# airball_sensor_board_v4.net
KiCad netlist of a schematic drawn in EAGLE
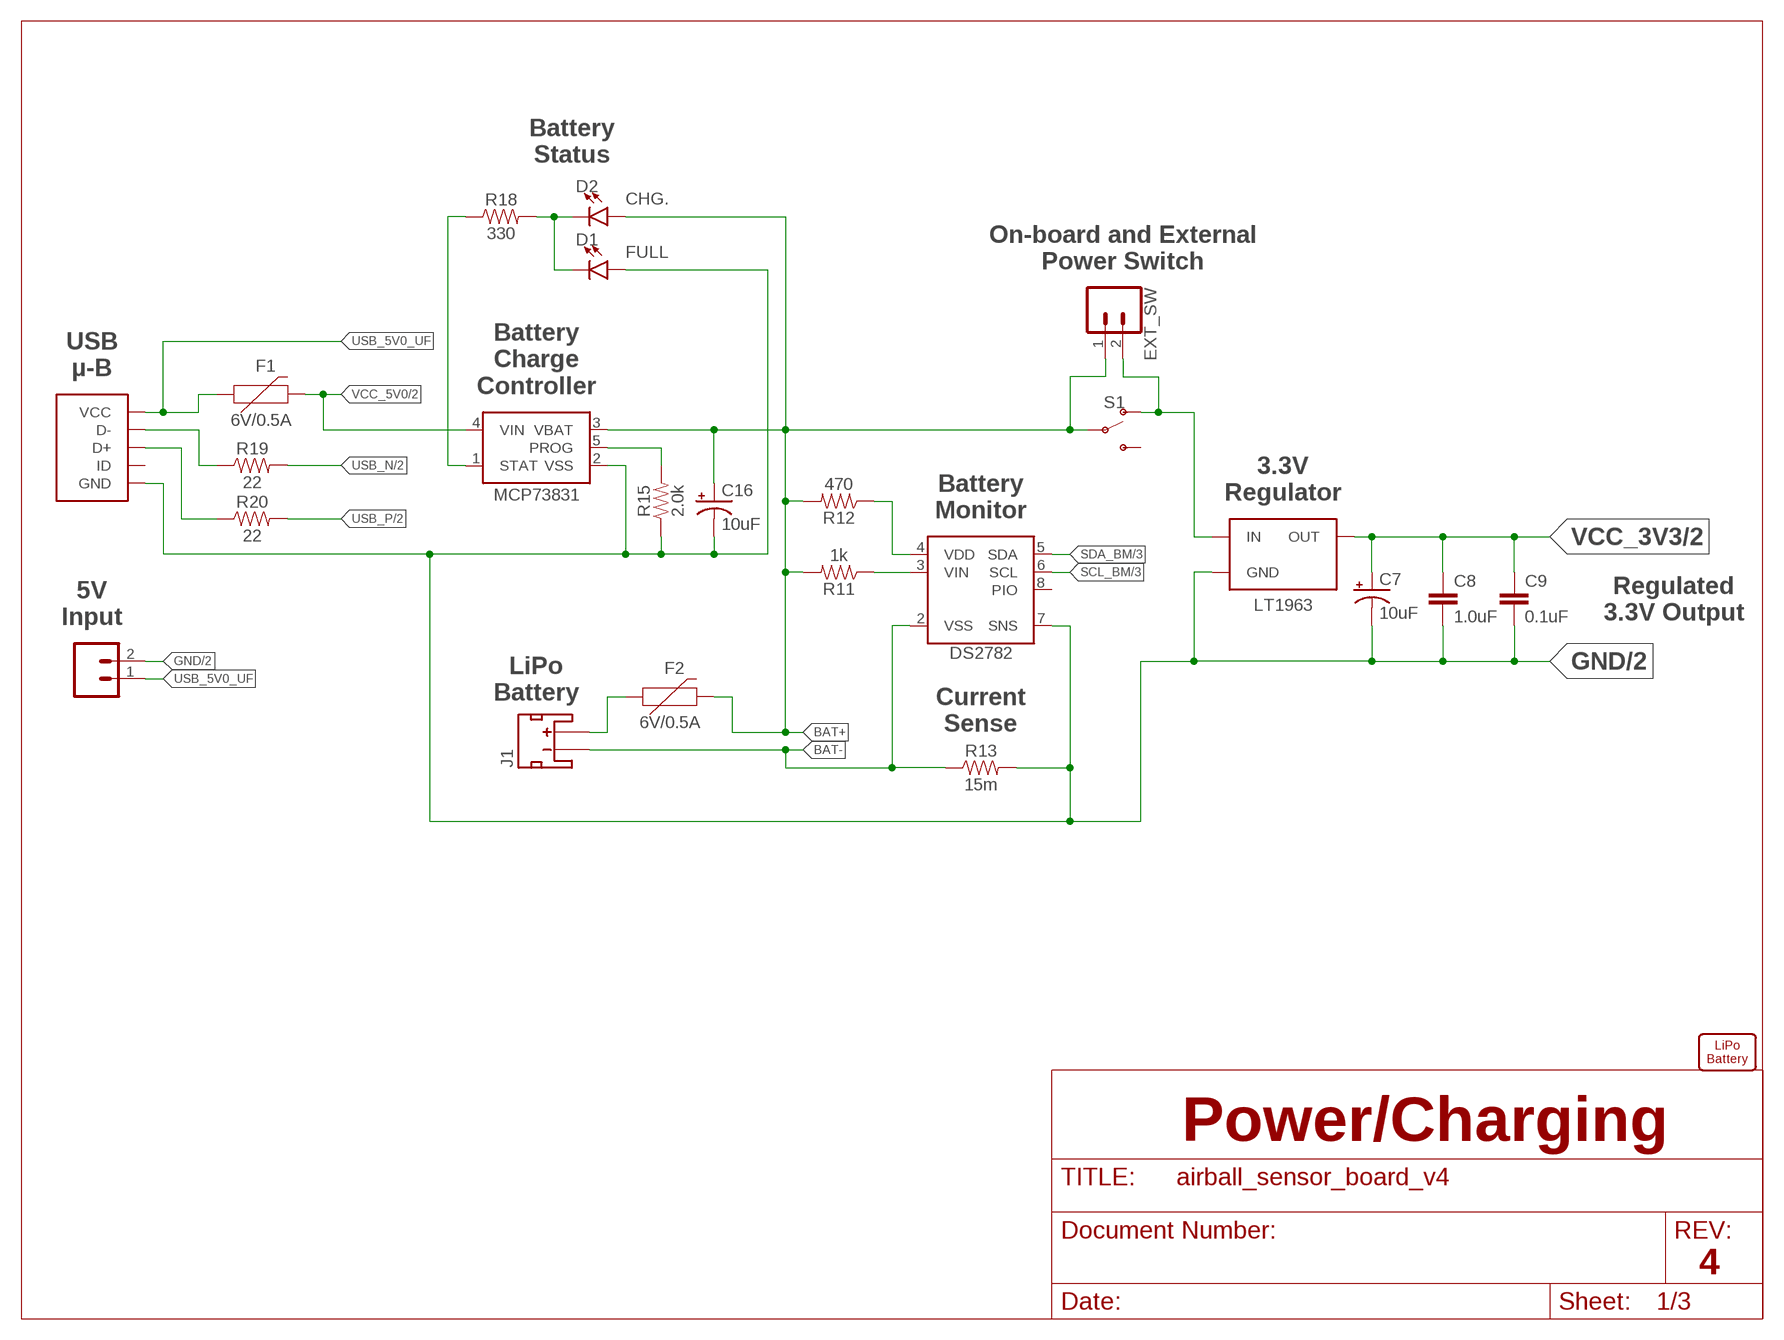
[diagram p0: schematic, sheet 1]
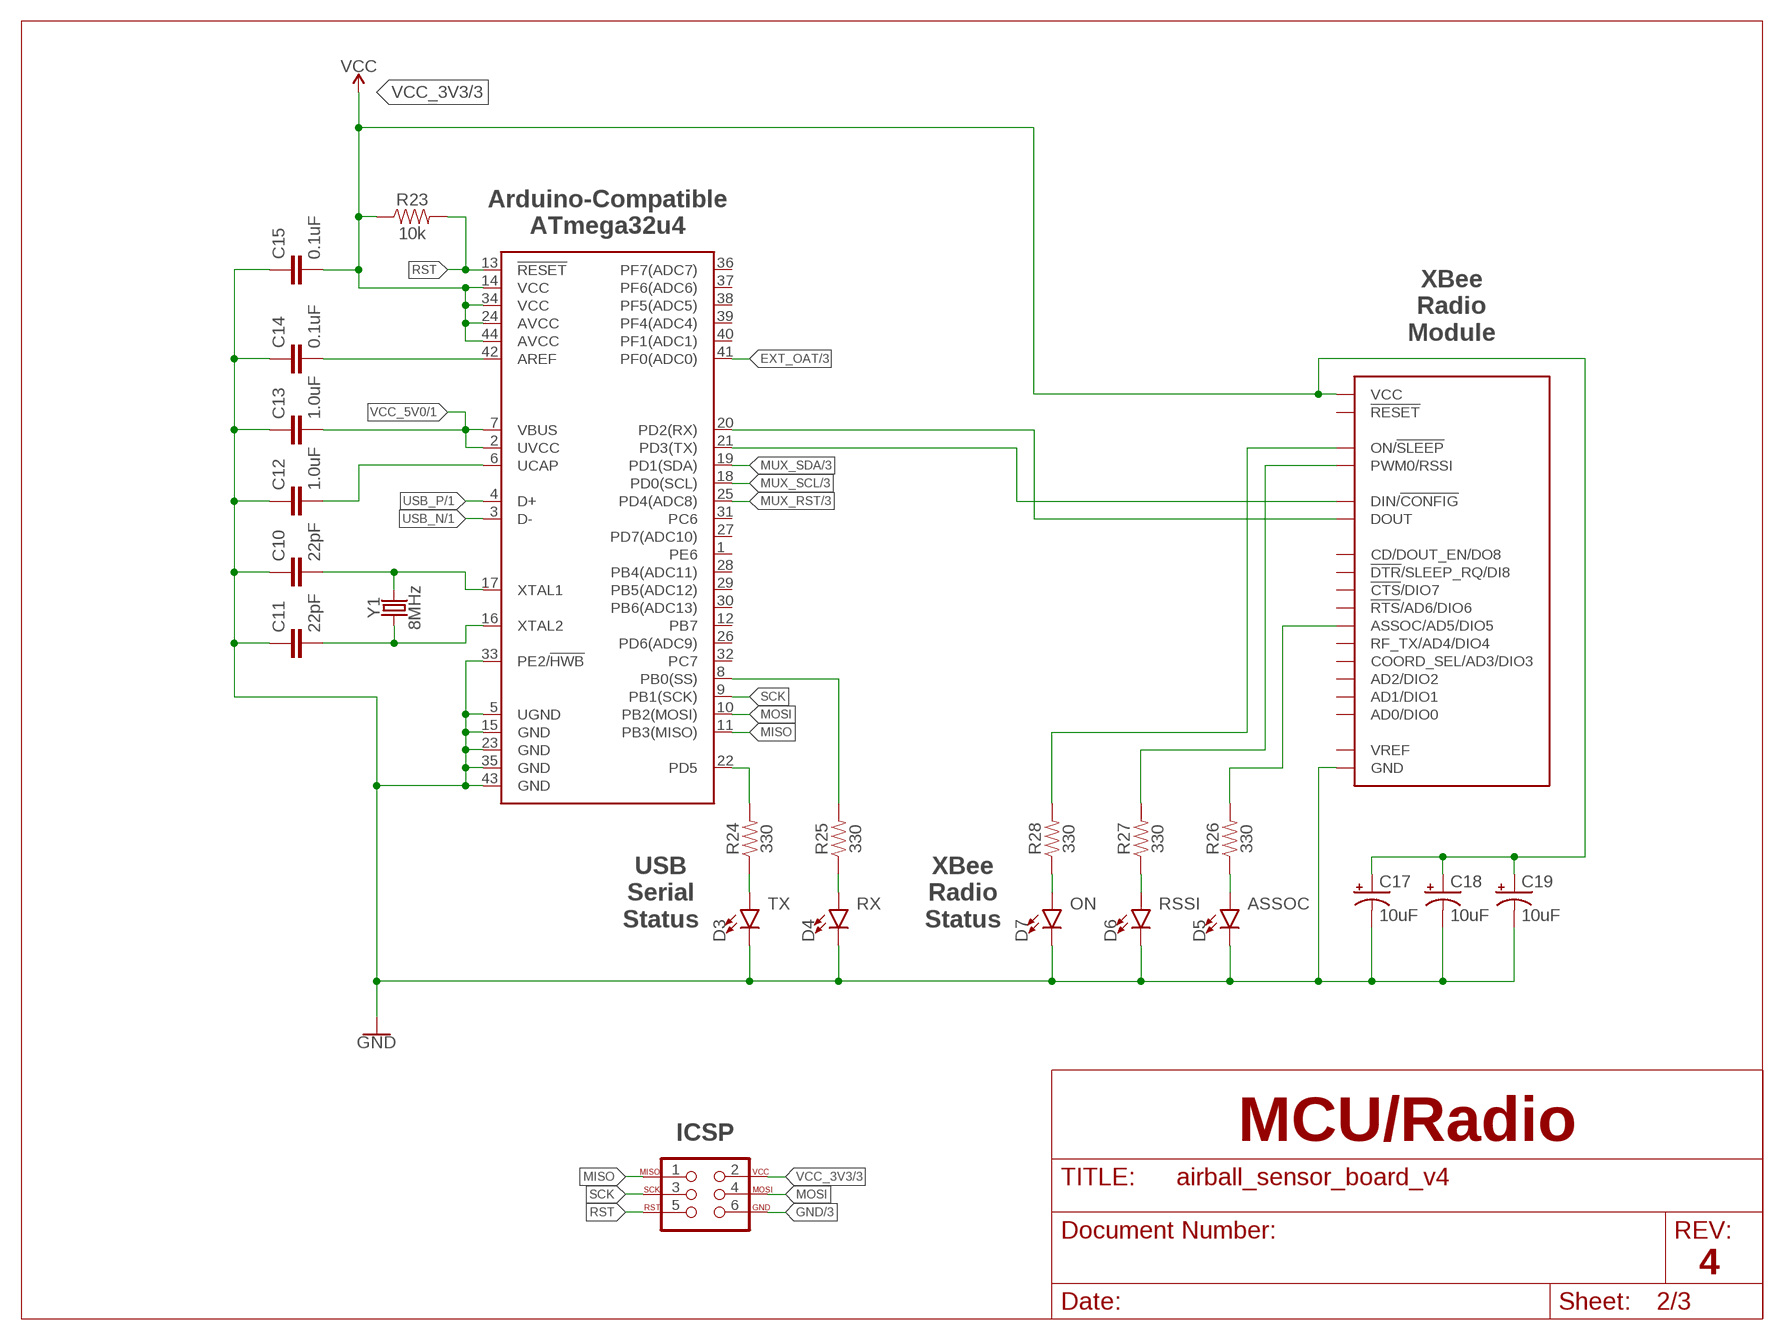
[diagram p1: schematic, sheet 2]
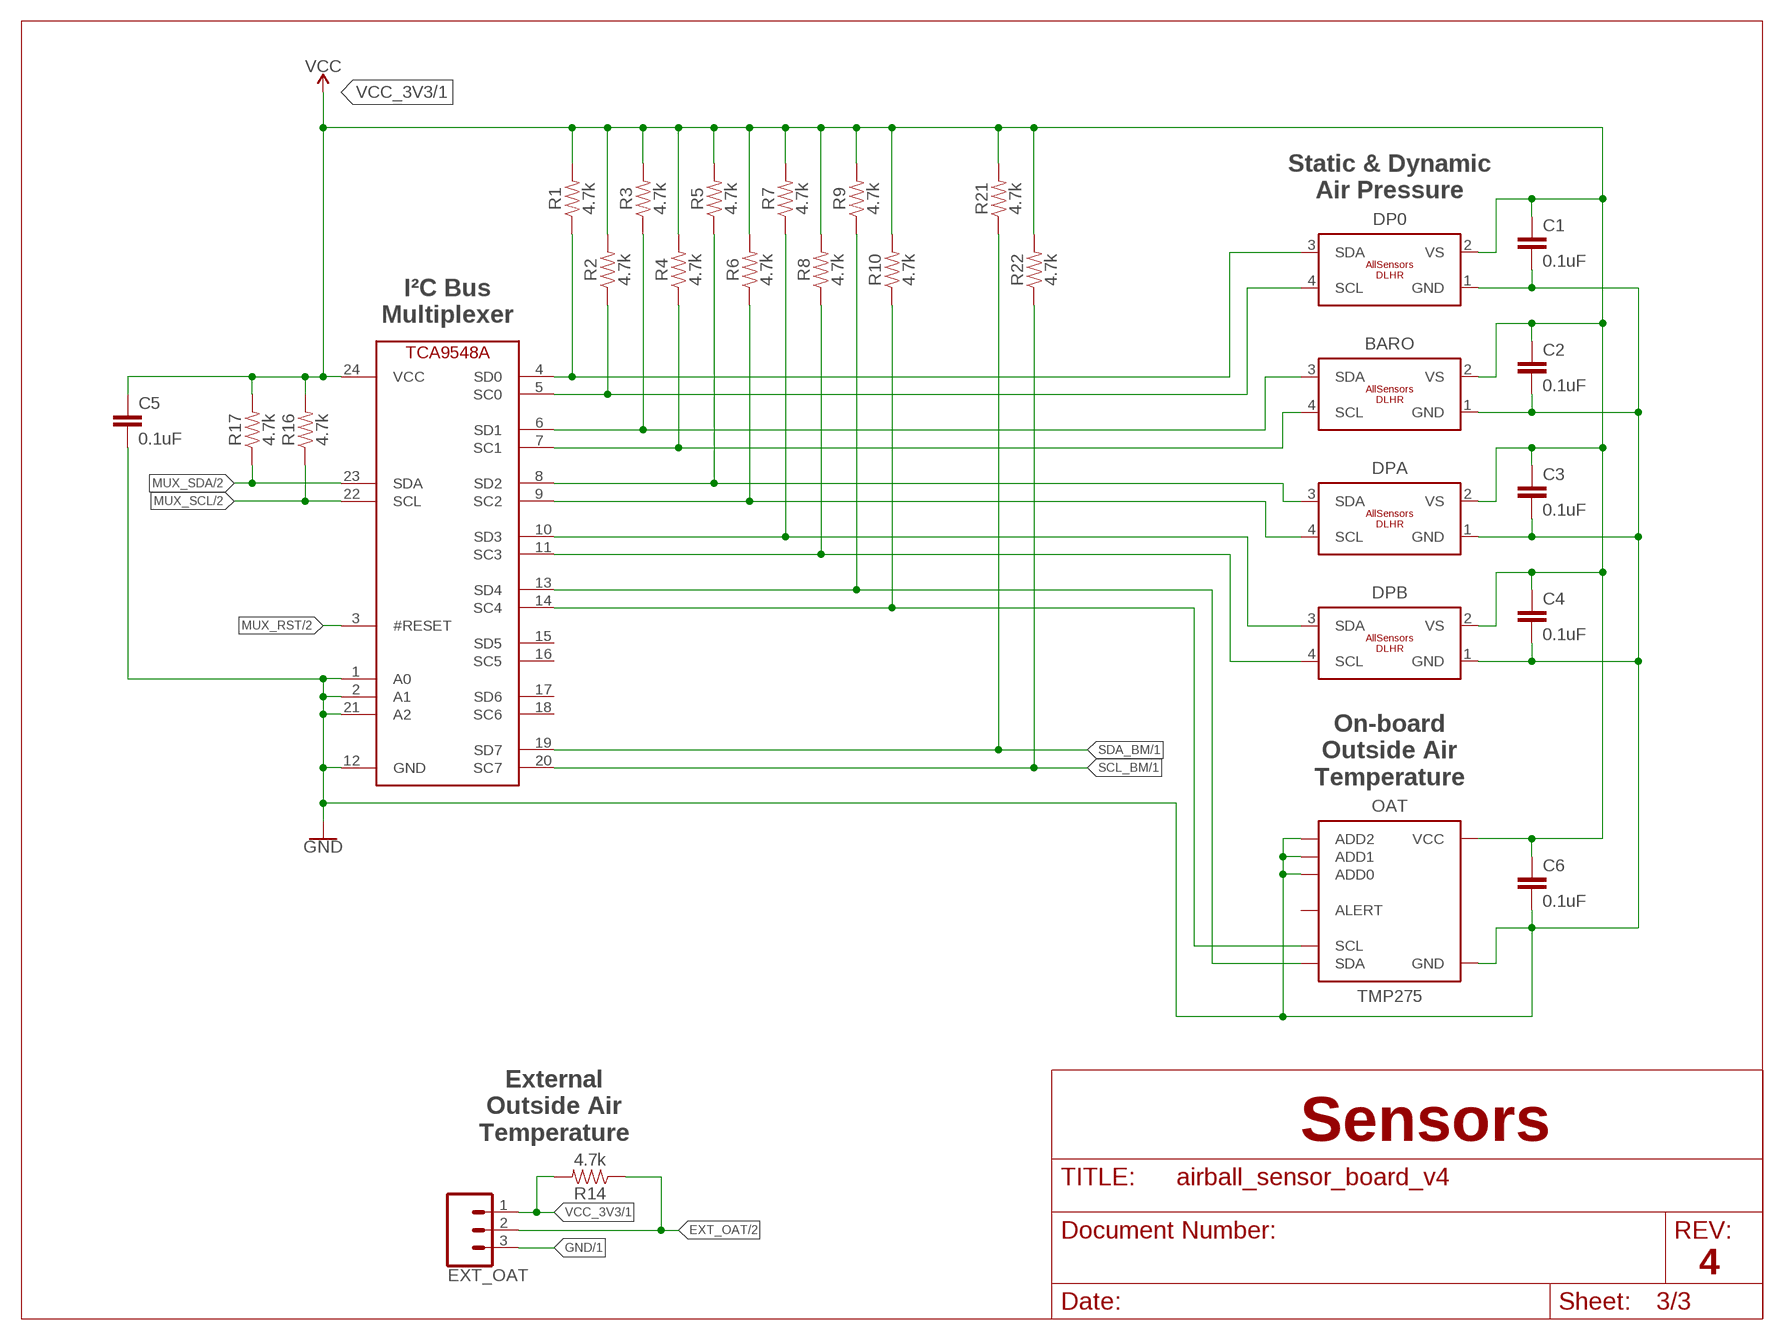
[diagram p2: schematic, sheet 3]

(export (version "E")
  (design (tool "Eeschema 10.0.6"))
  (components
    (comp (ref "BM")
      (value "DS2782")
      (footprint "eagle-import:TSSOP8")
      (libsource (lib "eagle-import") (part "DS2782"))
    )
    (comp (ref "C7")
      (value "10uF")
      (footprint "eagle-import:EIA3216")
      (libsource (lib "eagle-import") (part "10UF-POLAR-EIA3216-16V-10%(TANT)"))
    )
    (comp (ref "C8")
      (value "1.0uF")
      (footprint "eagle-import:0603")
      (libsource (lib "eagle-import") (part "1.0UF-0603-16V-10%"))
    )
    (comp (ref "C9")
      (value "0.1uF")
      (footprint "eagle-import:0603")
      (libsource (lib "eagle-import") (part "0.1UF-0603-25V-5%"))
    )
    (comp (ref "C16")
      (value "10uF")
      (footprint "eagle-import:EIA3216")
      (libsource (lib "eagle-import") (part "10UF-POLAR-EIA3216-16V-10%(TANT)"))
    )
    (comp (ref "CC")
      (value "MCP73831")
      (footprint "eagle-import:SOT23-5")
      (libsource (lib "eagle-import") (part "MCP73831"))
    )
    (comp (ref "D1")
      (value "LED0603")
      (footprint "eagle-import:LED-0603")
      (libsource (lib "eagle-import") (part "LED0603"))
    )
    (comp (ref "D2")
      (value "LED0603")
      (footprint "eagle-import:LED-0603")
      (libsource (lib "eagle-import") (part "LED0603"))
    )
    (comp (ref "EXT_POWER")
      (value "CONN_02")
      (footprint "eagle-import:1X02")
      (libsource (lib "eagle-import") (part "CONN_02"))
    )
    (comp (ref "EXT_SW")
      (value "CONN_02")
      (footprint "eagle-import:1X02")
      (libsource (lib "eagle-import") (part "CONN_02"))
    )
    (comp (ref "F1")
      (value "6V/0.5A")
      (footprint "eagle-import:1206")
      (libsource (lib "eagle-import") (part "PPTC_HALF-AMP"))
    )
    (comp (ref "F2")
      (value "6V/0.5A")
      (footprint "eagle-import:1206")
      (libsource (lib "eagle-import") (part "PPTC_HALF-AMP"))
    )
    (comp (ref "J1")
      (value "JST_2MM_MALE")
      (footprint "eagle-import:JST-2-SMD")
      (libsource (lib "eagle-import") (part "JST_2MM_MALE"))
    )
    (comp (ref "JP1")
      (value "USB_MICROB_PLUG")
      (footprint "eagle-import:USB_MICRO_B_TYCO")
      (libsource (lib "eagle-import") (part "USB_MICROB_PLUG"))
    )
    (comp (ref "R11")
      (value "1k")
      (footprint "eagle-import:0603")
      (libsource (lib "eagle-import") (part "1KOHM-0603-1/10W-1%"))
    )
    (comp (ref "R12")
      (value "470")
      (footprint "eagle-import:0603")
      (libsource (lib "eagle-import") (part "470OHM-0603-1/10W-1%"))
    )
    (comp (ref "R13")
      (value "15m")
      (footprint "eagle-import:1206")
      (libsource (lib "eagle-import") (part "RESISTOR1206"))
    )
    (comp (ref "R15")
      (value "2.0k")
      (footprint "eagle-import:0603")
      (libsource (lib "eagle-import") (part "2.0KOHM-0603-1/10W-5%"))
    )
    (comp (ref "R18")
      (value "330")
      (footprint "eagle-import:0603")
      (libsource (lib "eagle-import") (part "330OHM-0603-1/10W-1%"))
    )
    (comp (ref "R19")
      (value "22")
      (footprint "eagle-import:0603")
      (libsource (lib "eagle-import") (part "22OHM-0603-1/10W-1%"))
    )
    (comp (ref "R20")
      (value "22")
      (footprint "eagle-import:0603")
      (libsource (lib "eagle-import") (part "22OHM-0603-1/10W-1%"))
    )
    (comp (ref "S1")
      (value "SWITCH-SPDT-SMD-RIGHT-ANGLE")
      (footprint "eagle-import:SWITCH_SPST_SMD_A")
      (libsource (lib "eagle-import") (part "SWITCH-SPDT-SMD-RIGHT-ANGLE"))
    )
    (comp (ref "U$3")
      (value "LIPO_BATTERY_OUTLINE-1000MAH")
      (footprint "eagle-import:SPARKFUN_LIPO_1000MAH")
      (libsource (lib "eagle-import") (part "LIPO_BATTERY_OUTLINE-1000MAH"))
    )
    (comp (ref "VREG")
      (value "LT1963")
      (footprint "eagle-import:SOT223-3")
      (libsource (lib "eagle-import") (part "LT1963"))
    )
    (comp (ref "BARO")
      (value "ALLSENSORS_DLHR_I2C-E1BD")
      (footprint "eagle-import:ALLSENSORS_E1BD")
      (libsource (lib "eagle-import") (part "ALLSENSORS_DLHR_I2C-E1BD"))
    )
    (comp (ref "C1")
      (value "0.1uF")
      (footprint "eagle-import:0603")
      (libsource (lib "eagle-import") (part "0.1UF-0603-25V-5%"))
    )
    (comp (ref "C2")
      (value "0.1uF")
      (footprint "eagle-import:0603")
      (libsource (lib "eagle-import") (part "0.1UF-0603-25V-5%"))
    )
    (comp (ref "C3")
      (value "0.1uF")
      (footprint "eagle-import:0603")
      (libsource (lib "eagle-import") (part "0.1UF-0603-25V-5%"))
    )
    (comp (ref "C4")
      (value "0.1uF")
      (footprint "eagle-import:0603")
      (libsource (lib "eagle-import") (part "0.1UF-0603-25V-5%"))
    )
    (comp (ref "C5")
      (value "0.1uF")
      (footprint "eagle-import:0603")
      (libsource (lib "eagle-import") (part "0.1UF-0603-25V-5%"))
    )
    (comp (ref "C6")
      (value "0.1uF")
      (footprint "eagle-import:0603")
      (libsource (lib "eagle-import") (part "0.1UF-0603-25V-5%"))
    )
    (comp (ref "DP0")
      (value "ALLSENSORS_DLHR_I2C-E1BD")
      (footprint "eagle-import:ALLSENSORS_E1BD")
      (libsource (lib "eagle-import") (part "ALLSENSORS_DLHR_I2C-E1BD"))
    )
    (comp (ref "DPA")
      (value "ALLSENSORS_DLHR_I2C-E1BD")
      (footprint "eagle-import:ALLSENSORS_E1BD")
      (libsource (lib "eagle-import") (part "ALLSENSORS_DLHR_I2C-E1BD"))
    )
    (comp (ref "DPB")
      (value "ALLSENSORS_DLHR_I2C-E1BD")
      (footprint "eagle-import:ALLSENSORS_E1BD")
      (libsource (lib "eagle-import") (part "ALLSENSORS_DLHR_I2C-E1BD"))
    )
    (comp (ref "EXT_OAT")
      (value "CONN_03")
      (footprint "eagle-import:1X03")
      (libsource (lib "eagle-import") (part "CONN_03"))
    )
    (comp (ref "MUX")
      (value "TCA9548ATSSOP24")
      (footprint "eagle-import:TSSOP24")
      (libsource (lib "eagle-import") (part "TCA9548ATSSOP24"))
    )
    (comp (ref "OAT")
      (value "TMP275")
      (footprint "eagle-import:SOIC8")
      (libsource (lib "eagle-import") (part "LM75-8PIN"))
    )
    (comp (ref "R1")
      (value "4.7k")
      (footprint "eagle-import:0603")
      (libsource (lib "eagle-import") (part "4.7KOHM-0603-1/10W-1%"))
    )
    (comp (ref "R2")
      (value "4.7k")
      (footprint "eagle-import:0603")
      (libsource (lib "eagle-import") (part "4.7KOHM-0603-1/10W-1%"))
    )
    (comp (ref "R3")
      (value "4.7k")
      (footprint "eagle-import:0603")
      (libsource (lib "eagle-import") (part "4.7KOHM-0603-1/10W-1%"))
    )
    (comp (ref "R4")
      (value "4.7k")
      (footprint "eagle-import:0603")
      (libsource (lib "eagle-import") (part "4.7KOHM-0603-1/10W-1%"))
    )
    (comp (ref "R5")
      (value "4.7k")
      (footprint "eagle-import:0603")
      (libsource (lib "eagle-import") (part "4.7KOHM-0603-1/10W-1%"))
    )
    (comp (ref "R6")
      (value "4.7k")
      (footprint "eagle-import:0603")
      (libsource (lib "eagle-import") (part "4.7KOHM-0603-1/10W-1%"))
    )
    (comp (ref "R7")
      (value "4.7k")
      (footprint "eagle-import:0603")
      (libsource (lib "eagle-import") (part "4.7KOHM-0603-1/10W-1%"))
    )
    (comp (ref "R8")
      (value "4.7k")
      (footprint "eagle-import:0603")
      (libsource (lib "eagle-import") (part "4.7KOHM-0603-1/10W-1%"))
    )
    (comp (ref "R9")
      (value "4.7k")
      (footprint "eagle-import:0603")
      (libsource (lib "eagle-import") (part "4.7KOHM-0603-1/10W-1%"))
    )
    (comp (ref "R10")
      (value "4.7k")
      (footprint "eagle-import:0603")
      (libsource (lib "eagle-import") (part "4.7KOHM-0603-1/10W-1%"))
    )
    (comp (ref "R14")
      (value "4.7k")
      (footprint "eagle-import:0603")
      (libsource (lib "eagle-import") (part "4.7KOHM-0603-1/10W-1%"))
    )
    (comp (ref "R16")
      (value "4.7k")
      (footprint "eagle-import:0603")
      (libsource (lib "eagle-import") (part "4.7KOHM-0603-1/10W-1%"))
    )
    (comp (ref "R17")
      (value "4.7k")
      (footprint "eagle-import:0603")
      (libsource (lib "eagle-import") (part "4.7KOHM-0603-1/10W-1%"))
    )
    (comp (ref "R21")
      (value "4.7k")
      (footprint "eagle-import:0603")
      (libsource (lib "eagle-import") (part "4.7KOHM-0603-1/10W-1%"))
    )
    (comp (ref "R22")
      (value "4.7k")
      (footprint "eagle-import:0603")
      (libsource (lib "eagle-import") (part "4.7KOHM-0603-1/10W-1%"))
    )
    (comp (ref "C10")
      (value "22pF")
      (footprint "eagle-import:0603")
      (libsource (lib "eagle-import") (part "22PF-0603-50V-5%"))
    )
    (comp (ref "C11")
      (value "22pF")
      (footprint "eagle-import:0603")
      (libsource (lib "eagle-import") (part "22PF-0603-50V-5%"))
    )
    (comp (ref "C12")
      (value "1.0uF")
      (footprint "eagle-import:0603")
      (libsource (lib "eagle-import") (part "1.0UF-0603-16V-10%"))
    )
    (comp (ref "C13")
      (value "1.0uF")
      (footprint "eagle-import:0603")
      (libsource (lib "eagle-import") (part "1.0UF-0603-16V-10%"))
    )
    (comp (ref "C14")
      (value "0.1uF")
      (footprint "eagle-import:0603")
      (libsource (lib "eagle-import") (part "0.1UF-0603-25V-5%"))
    )
    (comp (ref "C15")
      (value "0.1uF")
      (footprint "eagle-import:0603")
      (libsource (lib "eagle-import") (part "0.1UF-0603-25V-5%"))
    )
    (comp (ref "C17")
      (value "10uF")
      (footprint "eagle-import:EIA3216")
      (libsource (lib "eagle-import") (part "10UF-POLAR-EIA3216-16V-10%(TANT)"))
    )
    (comp (ref "C18")
      (value "10uF")
      (footprint "eagle-import:EIA3216")
      (libsource (lib "eagle-import") (part "10UF-POLAR-EIA3216-16V-10%(TANT)"))
    )
    (comp (ref "C19")
      (value "10uF")
      (footprint "eagle-import:EIA3216")
      (libsource (lib "eagle-import") (part "10UF-POLAR-EIA3216-16V-10%(TANT)"))
    )
    (comp (ref "D3")
      (value "LED0603")
      (footprint "eagle-import:LED-0603")
      (libsource (lib "eagle-import") (part "LED0603"))
    )
    (comp (ref "D4")
      (value "LED0603")
      (footprint "eagle-import:LED-0603")
      (libsource (lib "eagle-import") (part "LED0603"))
    )
    (comp (ref "D5")
      (value "LED0603")
      (footprint "eagle-import:LED-0603")
      (libsource (lib "eagle-import") (part "LED0603"))
    )
    (comp (ref "D6")
      (value "LED0603")
      (footprint "eagle-import:LED-0603")
      (libsource (lib "eagle-import") (part "LED0603"))
    )
    (comp (ref "D7")
      (value "LED0603")
      (footprint "eagle-import:LED-0603")
      (libsource (lib "eagle-import") (part "LED0603"))
    )
    (comp (ref "ICSP")
      (value "AVR_SPI_PROG_3X2PTH")
      (footprint "eagle-import:2X3")
      (libsource (lib "eagle-import") (part "AVR_SPI_PROG_3X2PTH"))
    )
    (comp (ref "MCU")
      (value "32U4")
      (footprint "eagle-import:TQFP44")
      (libsource (lib "eagle-import") (part "ATMEGA32U4TQFP-44"))
    )
    (comp (ref "R23")
      (value "10k")
      (footprint "eagle-import:0603")
      (libsource (lib "eagle-import") (part "10KOHM-0603-1/10W-1%"))
    )
    (comp (ref "R24")
      (value "330")
      (footprint "eagle-import:0603")
      (libsource (lib "eagle-import") (part "330OHM-0603-1/10W-1%"))
    )
    (comp (ref "R25")
      (value "330")
      (footprint "eagle-import:0603")
      (libsource (lib "eagle-import") (part "330OHM-0603-1/10W-1%"))
    )
    (comp (ref "R26")
      (value "330")
      (footprint "eagle-import:0603")
      (libsource (lib "eagle-import") (part "330OHM-0603-1/10W-1%"))
    )
    (comp (ref "R27")
      (value "330")
      (footprint "eagle-import:0603")
      (libsource (lib "eagle-import") (part "330OHM-0603-1/10W-1%"))
    )
    (comp (ref "R28")
      (value "330")
      (footprint "eagle-import:0603")
      (libsource (lib "eagle-import") (part "330OHM-0603-1/10W-1%"))
    )
    (comp (ref "XBEE")
      (value "XBEE-PRO-SMD")
      (footprint "eagle-import:XBEE-PRO-SMD")
      (libsource (lib "eagle-import") (part "XBEE-PRO-SMD"))
    )
    (comp (ref "Y1")
      (value "8MHz")
      (footprint "eagle-import:CRYSTAL-SMD-5X3.2-4PAD")
      (libsource (lib "eagle-import") (part "CRYSTAL-8MHZSMD-5X3.2"))
    )
  )
  (nets
    (net (code "1") (name "BAT+") (class "Default")
      (node (ref "C16") (pin "+") (pinfunction "+_+") (pintype "passive"))
      (node (ref "CC") (pin "3") (pinfunction "VBAT_3") (pintype "power_in"))
      (node (ref "D2") (pin "A") (pinfunction "A_A") (pintype "passive"))
      (node (ref "EXT_SW") (pin "1") (pinfunction "1_1") (pintype "passive"))
      (node (ref "F2") (pin "2") (pinfunction "2_2") (pintype "bidirectional"))
      (node (ref "R11") (pin "2") (pinfunction "2_2") (pintype "passive"))
      (node (ref "R12") (pin "2") (pinfunction "2_2") (pintype "passive"))
      (node (ref "S1") (pin "2") (pinfunction "P_2") (pintype "passive"))
    )
    (net (code "2") (name "BAT-") (class "Default")
      (node (ref "BM") (pin "2") (pinfunction "VSS_2") (pintype "power_in"))
      (node (ref "J1") (pin "1") (pinfunction "-_1") (pintype "bidirectional"))
      (node (ref "R13") (pin "1") (pinfunction "1_1") (pintype "passive"))
    )
    (net (code "3") (name "EXT_OAT") (class "Default")
      (node (ref "EXT_OAT") (pin "2") (pinfunction "2_2") (pintype "passive"))
      (node (ref "MCU") (pin "41") (pinfunction "PF0(ADC0)_41") (pintype "bidirectional"))
      (node (ref "R14") (pin "1") (pinfunction "1_1") (pintype "passive"))
    )
    (net (code "4") (name "GND") (class "Default")
      (node (ref "BARO") (pin "1") (pinfunction "GND_1") (pintype "power_in"))
      (node (ref "BM") (pin "7") (pinfunction "SNS_7") (pintype "power_in"))
      (node (ref "C1") (pin "2") (pinfunction "2_2") (pintype "passive"))
      (node (ref "C10") (pin "1") (pinfunction "1_1") (pintype "passive"))
      (node (ref "C11") (pin "1") (pinfunction "1_1") (pintype "passive"))
      (node (ref "C12") (pin "1") (pinfunction "1_1") (pintype "passive"))
      (node (ref "C13") (pin "1") (pinfunction "1_1") (pintype "passive"))
      (node (ref "C14") (pin "1") (pinfunction "1_1") (pintype "passive"))
      (node (ref "C15") (pin "1") (pinfunction "1_1") (pintype "passive"))
      (node (ref "C16") (pin "-") (pinfunction "-_-") (pintype "passive"))
      (node (ref "C17") (pin "-") (pinfunction "-_-") (pintype "passive"))
      (node (ref "C18") (pin "-") (pinfunction "-_-") (pintype "passive"))
      (node (ref "C19") (pin "-") (pinfunction "-_-") (pintype "passive"))
      (node (ref "C2") (pin "2") (pinfunction "2_2") (pintype "passive"))
      (node (ref "C3") (pin "2") (pinfunction "2_2") (pintype "passive"))
      (node (ref "C4") (pin "2") (pinfunction "2_2") (pintype "passive"))
      (node (ref "C5") (pin "2") (pinfunction "2_2") (pintype "passive"))
      (node (ref "C6") (pin "2") (pinfunction "2_2") (pintype "passive"))
      (node (ref "C7") (pin "-") (pinfunction "-_-") (pintype "passive"))
      (node (ref "C8") (pin "2") (pinfunction "2_2") (pintype "passive"))
      (node (ref "C9") (pin "2") (pinfunction "2_2") (pintype "passive"))
      (node (ref "CC") (pin "2") (pinfunction "VSS_2") (pintype "power_in"))
      (node (ref "D1") (pin "A") (pinfunction "A_A") (pintype "passive"))
      (node (ref "D3") (pin "C") (pinfunction "C_C") (pintype "passive"))
      (node (ref "D4") (pin "C") (pinfunction "C_C") (pintype "passive"))
      (node (ref "D5") (pin "C") (pinfunction "C_C") (pintype "passive"))
      (node (ref "D6") (pin "C") (pinfunction "C_C") (pintype "passive"))
      (node (ref "D7") (pin "C") (pinfunction "C_C") (pintype "passive"))
      (node (ref "DP0") (pin "1") (pinfunction "GND_1") (pintype "power_in"))
      (node (ref "DPA") (pin "1") (pinfunction "GND_1") (pintype "power_in"))
      (node (ref "DPB") (pin "1") (pinfunction "GND_1") (pintype "power_in"))
      (node (ref "EXT_OAT") (pin "3") (pinfunction "3_3") (pintype "passive"))
      (node (ref "EXT_POWER") (pin "2") (pinfunction "2_2") (pintype "passive"))
      (node (ref "ICSP") (pin "6") (pinfunction "6_6") (pintype "passive"))
      (node (ref "JP1") (pin "5") (pinfunction "GND_5") (pintype "power_in"))
      (node (ref "JP1") (pin "SH@1") (pinfunction "GND_SH@1") (pintype "power_in"))
      (node (ref "JP1") (pin "SH@2") (pinfunction "GND_SH@2") (pintype "power_in"))
      (node (ref "JP1") (pin "SH@3") (pinfunction "GND_SH@3") (pintype "power_in"))
      (node (ref "JP1") (pin "SH@4") (pinfunction "GND_SH@4") (pintype "power_in"))
      (node (ref "MCU") (pin "15") (pinfunction "GND_15") (pintype "bidirectional"))
      (node (ref "MCU") (pin "23") (pinfunction "GND_23") (pintype "bidirectional"))
      (node (ref "MCU") (pin "33") (pinfunction "PE2/~{HWB}_33") (pintype "bidirectional"))
      (node (ref "MCU") (pin "35") (pinfunction "GND_35") (pintype "bidirectional"))
      (node (ref "MCU") (pin "43") (pinfunction "GND_43") (pintype "bidirectional"))
      (node (ref "MCU") (pin "5") (pinfunction "UGND_5") (pintype "bidirectional"))
      (node (ref "MUX") (pin "1") (pinfunction "A0_1") (pintype "bidirectional"))
      (node (ref "MUX") (pin "12") (pinfunction "GND_12") (pintype "bidirectional"))
      (node (ref "MUX") (pin "2") (pinfunction "A1_2") (pintype "bidirectional"))
      (node (ref "MUX") (pin "21") (pinfunction "A2_21") (pintype "bidirectional"))
      (node (ref "OAT") (pin "4") (pinfunction "GND_4") (pintype "power_in"))
      (node (ref "OAT") (pin "5") (pinfunction "ADD2_5") (pintype "input"))
      (node (ref "OAT") (pin "6") (pinfunction "ADD1_6") (pintype "input"))
      (node (ref "OAT") (pin "7") (pinfunction "ADD0_7") (pintype "input"))
      (node (ref "R13") (pin "2") (pinfunction "2_2") (pintype "passive"))
      (node (ref "R15") (pin "1") (pinfunction "1_1") (pintype "passive"))
      (node (ref "VREG") (pin "2") (pinfunction "GND_2") (pintype "power_in"))
      (node (ref "VREG") (pin "TAB") (pinfunction "GND_TAB") (pintype "power_in"))
      (node (ref "XBEE") (pin "10") (pinfunction "GND_10") (pintype "power_in"))
    )
    (net (code "5") (name "MISO") (class "Default")
      (node (ref "ICSP") (pin "1") (pinfunction "1_1") (pintype "passive"))
      (node (ref "MCU") (pin "11") (pinfunction "PB3(MISO)_11") (pintype "bidirectional"))
    )
    (net (code "6") (name "MOSI") (class "Default")
      (node (ref "ICSP") (pin "4") (pinfunction "4_4") (pintype "passive"))
      (node (ref "MCU") (pin "10") (pinfunction "PB2(MOSI)_10") (pintype "bidirectional"))
    )
    (net (code "7") (name "MUX_RST") (class "Default")
      (node (ref "MCU") (pin "25") (pinfunction "PD4(ADC8)_25") (pintype "bidirectional"))
      (node (ref "MUX") (pin "3") (pinfunction "#RESET_3") (pintype "bidirectional"))
    )
    (net (code "8") (name "MUX_SCL") (class "Default")
      (node (ref "MCU") (pin "18") (pinfunction "PD0(SCL)_18") (pintype "bidirectional"))
      (node (ref "MUX") (pin "22") (pinfunction "SCL_22") (pintype "bidirectional"))
      (node (ref "R16") (pin "1") (pinfunction "1_1") (pintype "passive"))
    )
    (net (code "9") (name "MUX_SDA") (class "Default")
      (node (ref "MCU") (pin "19") (pinfunction "PD1(SDA)_19") (pintype "bidirectional"))
      (node (ref "MUX") (pin "23") (pinfunction "SDA_23") (pintype "bidirectional"))
      (node (ref "R17") (pin "1") (pinfunction "1_1") (pintype "passive"))
    )
    (net (code "10") (name "Net-(BARO-SCL)") (class "Default")
      (node (ref "BARO") (pin "4") (pinfunction "SCL_4") (pintype "bidirectional"))
      (node (ref "MUX") (pin "7") (pinfunction "SC1_7") (pintype "bidirectional"))
      (node (ref "R4") (pin "1") (pinfunction "1_1") (pintype "passive"))
    )
    (net (code "11") (name "Net-(BARO-SDA)") (class "Default")
      (node (ref "BARO") (pin "3") (pinfunction "SDA_3") (pintype "bidirectional"))
      (node (ref "MUX") (pin "6") (pinfunction "SD1_6") (pintype "bidirectional"))
      (node (ref "R3") (pin "1") (pinfunction "1_1") (pintype "passive"))
    )
    (net (code "12") (name "Net-(BM-VDD)") (class "Default")
      (node (ref "BM") (pin "4") (pinfunction "VDD_4") (pintype "power_in"))
      (node (ref "R12") (pin "1") (pinfunction "1_1") (pintype "passive"))
    )
    (net (code "13") (name "Net-(BM-VIN)") (class "Default")
      (node (ref "BM") (pin "3") (pinfunction "VIN_3") (pintype "power_in"))
      (node (ref "R11") (pin "1") (pinfunction "1_1") (pintype "passive"))
    )
    (net (code "14") (name "Net-(CC-PROG)") (class "Default")
      (node (ref "CC") (pin "5") (pinfunction "PROG_5") (pintype "input"))
      (node (ref "R15") (pin "2") (pinfunction "2_2") (pintype "passive"))
    )
    (net (code "15") (name "Net-(CC-STAT)") (class "Default")
      (node (ref "CC") (pin "1") (pinfunction "STAT_1") (pintype "output"))
      (node (ref "R18") (pin "1") (pinfunction "1_1") (pintype "passive"))
    )
    (net (code "16") (name "Net-(D1-PadC)") (class "Default")
      (node (ref "D1") (pin "C") (pinfunction "C_C") (pintype "passive"))
      (node (ref "D2") (pin "C") (pinfunction "C_C") (pintype "passive"))
      (node (ref "R18") (pin "2") (pinfunction "2_2") (pintype "passive"))
    )
    (net (code "17") (name "Net-(D3-PadA)") (class "Default")
      (node (ref "D3") (pin "A") (pinfunction "A_A") (pintype "passive"))
      (node (ref "R24") (pin "1") (pinfunction "1_1") (pintype "passive"))
    )
    (net (code "18") (name "Net-(D4-PadA)") (class "Default")
      (node (ref "D4") (pin "A") (pinfunction "A_A") (pintype "passive"))
      (node (ref "R25") (pin "1") (pinfunction "1_1") (pintype "passive"))
    )
    (net (code "19") (name "Net-(D5-PadA)") (class "Default")
      (node (ref "D5") (pin "A") (pinfunction "A_A") (pintype "passive"))
      (node (ref "R26") (pin "1") (pinfunction "1_1") (pintype "passive"))
    )
    (net (code "20") (name "Net-(D6-PadA)") (class "Default")
      (node (ref "D6") (pin "A") (pinfunction "A_A") (pintype "passive"))
      (node (ref "R27") (pin "1") (pinfunction "1_1") (pintype "passive"))
    )
    (net (code "21") (name "Net-(D7-PadA)") (class "Default")
      (node (ref "D7") (pin "A") (pinfunction "A_A") (pintype "passive"))
      (node (ref "R28") (pin "1") (pinfunction "1_1") (pintype "passive"))
    )
    (net (code "22") (name "Net-(DP0-SCL)") (class "Default")
      (node (ref "DP0") (pin "4") (pinfunction "SCL_4") (pintype "bidirectional"))
      (node (ref "MUX") (pin "5") (pinfunction "SC0_5") (pintype "bidirectional"))
      (node (ref "R2") (pin "1") (pinfunction "1_1") (pintype "passive"))
    )
    (net (code "23") (name "Net-(DP0-SDA)") (class "Default")
      (node (ref "DP0") (pin "3") (pinfunction "SDA_3") (pintype "bidirectional"))
      (node (ref "MUX") (pin "4") (pinfunction "SD0_4") (pintype "bidirectional"))
      (node (ref "R1") (pin "1") (pinfunction "1_1") (pintype "passive"))
    )
    (net (code "24") (name "Net-(DPA-SCL)") (class "Default")
      (node (ref "DPA") (pin "4") (pinfunction "SCL_4") (pintype "bidirectional"))
      (node (ref "MUX") (pin "9") (pinfunction "SC2_9") (pintype "bidirectional"))
      (node (ref "R6") (pin "1") (pinfunction "1_1") (pintype "passive"))
    )
    (net (code "25") (name "Net-(DPA-SDA)") (class "Default")
      (node (ref "DPA") (pin "3") (pinfunction "SDA_3") (pintype "bidirectional"))
      (node (ref "MUX") (pin "8") (pinfunction "SD2_8") (pintype "bidirectional"))
      (node (ref "R5") (pin "1") (pinfunction "1_1") (pintype "passive"))
    )
    (net (code "26") (name "Net-(DPB-SCL)") (class "Default")
      (node (ref "DPB") (pin "4") (pinfunction "SCL_4") (pintype "bidirectional"))
      (node (ref "MUX") (pin "11") (pinfunction "SC3_11") (pintype "bidirectional"))
      (node (ref "R8") (pin "1") (pinfunction "1_1") (pintype "passive"))
    )
    (net (code "27") (name "Net-(DPB-SDA)") (class "Default")
      (node (ref "DPB") (pin "3") (pinfunction "SDA_3") (pintype "bidirectional"))
      (node (ref "MUX") (pin "10") (pinfunction "SD3_10") (pintype "bidirectional"))
      (node (ref "R7") (pin "1") (pinfunction "1_1") (pintype "passive"))
    )
    (net (code "28") (name "Net-(J1-+)") (class "Default")
      (node (ref "F2") (pin "1") (pinfunction "1_1") (pintype "bidirectional"))
      (node (ref "J1") (pin "2") (pinfunction "+_2") (pintype "bidirectional"))
    )
    (net (code "29") (name "Net-(JP1-D+)") (class "Default")
      (node (ref "JP1") (pin "3") (pinfunction "D+_3") (pintype "bidirectional"))
      (node (ref "R20") (pin "1") (pinfunction "1_1") (pintype "passive"))
    )
    (net (code "30") (name "Net-(JP1-D-)") (class "Default")
      (node (ref "JP1") (pin "2") (pinfunction "D-_2") (pintype "bidirectional"))
      (node (ref "R19") (pin "1") (pinfunction "1_1") (pintype "passive"))
    )
    (net (code "31") (name "Net-(MCU-AREF)") (class "Default")
      (node (ref "C14") (pin "2") (pinfunction "2_2") (pintype "passive"))
      (node (ref "MCU") (pin "42") (pinfunction "AREF_42") (pintype "bidirectional"))
    )
    (net (code "32") (name "Net-(MCU-PB0(SS))") (class "Default")
      (node (ref "MCU") (pin "8") (pinfunction "PB0(SS)_8") (pintype "bidirectional"))
      (node (ref "R25") (pin "2") (pinfunction "2_2") (pintype "passive"))
    )
    (net (code "33") (name "Net-(MCU-PD2(RX))") (class "Default")
      (node (ref "MCU") (pin "20") (pinfunction "PD2(RX)_20") (pintype "bidirectional"))
      (node (ref "XBEE") (pin "2") (pinfunction "DOUT_2") (pintype "output"))
    )
    (net (code "34") (name "Net-(MCU-PD3(TX))") (class "Default")
      (node (ref "MCU") (pin "21") (pinfunction "PD3(TX)_21") (pintype "bidirectional"))
      (node (ref "XBEE") (pin "3") (pinfunction "DIN/~{CONFIG}_3") (pintype "input"))
    )
    (net (code "35") (name "Net-(MCU-PD5)") (class "Default")
      (node (ref "MCU") (pin "22") (pinfunction "PD5_22") (pintype "bidirectional"))
      (node (ref "R24") (pin "2") (pinfunction "2_2") (pintype "passive"))
    )
    (net (code "36") (name "Net-(MCU-UCAP)") (class "Default")
      (node (ref "C12") (pin "2") (pinfunction "2_2") (pintype "passive"))
      (node (ref "MCU") (pin "6") (pinfunction "UCAP_6") (pintype "bidirectional"))
    )
    (net (code "37") (name "Net-(MCU-XTAL1)") (class "Default")
      (node (ref "C10") (pin "2") (pinfunction "2_2") (pintype "passive"))
      (node (ref "MCU") (pin "17") (pinfunction "XTAL1_17") (pintype "bidirectional"))
      (node (ref "Y1") (pin "3") (pinfunction "2_3") (pintype "passive"))
    )
    (net (code "38") (name "Net-(MCU-XTAL2)") (class "Default")
      (node (ref "C11") (pin "2") (pinfunction "2_2") (pintype "passive"))
      (node (ref "MCU") (pin "16") (pinfunction "XTAL2_16") (pintype "bidirectional"))
      (node (ref "Y1") (pin "1") (pinfunction "1_1") (pintype "passive"))
    )
    (net (code "39") (name "Net-(MUX-SC4)") (class "Default")
      (node (ref "MUX") (pin "14") (pinfunction "SC4_14") (pintype "bidirectional"))
      (node (ref "OAT") (pin "2") (pinfunction "SCL_2") (pintype "input"))
      (node (ref "R10") (pin "1") (pinfunction "1_1") (pintype "passive"))
    )
    (net (code "40") (name "Net-(MUX-SD4)") (class "Default")
      (node (ref "MUX") (pin "13") (pinfunction "SD4_13") (pintype "bidirectional"))
      (node (ref "OAT") (pin "1") (pinfunction "SDA_1") (pintype "bidirectional"))
      (node (ref "R9") (pin "1") (pinfunction "1_1") (pintype "passive"))
    )
    (net (code "41") (name "Net-(S1-O)") (class "Default")
      (node (ref "EXT_SW") (pin "2") (pinfunction "2_2") (pintype "passive"))
      (node (ref "S1") (pin "1") (pinfunction "O_1") (pintype "passive"))
      (node (ref "VREG") (pin "1") (pinfunction "IN_1") (pintype "power_in"))
    )
    (net (code "42") (name "Net-(XBEE-ASSOC{slash}AD5{slash}DIO5)") (class "Default")
      (node (ref "R26") (pin "2") (pinfunction "2_2") (pintype "passive"))
      (node (ref "XBEE") (pin "15") (pinfunction "ASSOC/AD5/DIO5_15") (pintype "bidirectional"))
    )
    (net (code "43") (name "Net-(XBEE-ON{slash}~{SLEEP})") (class "Default")
      (node (ref "R28") (pin "2") (pinfunction "2_2") (pintype "passive"))
      (node (ref "XBEE") (pin "13") (pinfunction "ON/~{SLEEP}_13") (pintype "output"))
    )
    (net (code "44") (name "Net-(XBEE-PWM0{slash}RSSI)") (class "Default")
      (node (ref "R27") (pin "2") (pinfunction "2_2") (pintype "passive"))
      (node (ref "XBEE") (pin "6") (pinfunction "PWM0/RSSI_6") (pintype "output"))
    )
    (net (code "45") (name "RST") (class "Default")
      (node (ref "ICSP") (pin "5") (pinfunction "5_5") (pintype "passive"))
      (node (ref "MCU") (pin "13") (pinfunction "~{RESET}_13") (pintype "bidirectional"))
      (node (ref "R23") (pin "2") (pinfunction "2_2") (pintype "passive"))
    )
    (net (code "46") (name "SCK") (class "Default")
      (node (ref "ICSP") (pin "3") (pinfunction "3_3") (pintype "passive"))
      (node (ref "MCU") (pin "9") (pinfunction "PB1(SCK)_9") (pintype "bidirectional"))
    )
    (net (code "47") (name "SCL_BM") (class "Default")
      (node (ref "BM") (pin "6") (pinfunction "SCL_6") (pintype "input"))
      (node (ref "MUX") (pin "20") (pinfunction "SC7_20") (pintype "bidirectional"))
      (node (ref "R22") (pin "1") (pinfunction "1_1") (pintype "passive"))
    )
    (net (code "48") (name "SDA_BM") (class "Default")
      (node (ref "BM") (pin "5") (pinfunction "SDA_5") (pintype "bidirectional"))
      (node (ref "MUX") (pin "19") (pinfunction "SD7_19") (pintype "bidirectional"))
      (node (ref "R21") (pin "1") (pinfunction "1_1") (pintype "passive"))
    )
    (net (code "49") (name "USB_5V0_UF") (class "Default")
      (node (ref "EXT_POWER") (pin "1") (pinfunction "1_1") (pintype "passive"))
      (node (ref "F1") (pin "1") (pinfunction "1_1") (pintype "bidirectional"))
      (node (ref "JP1") (pin "1") (pinfunction "VCC_1") (pintype "power_in"))
    )
    (net (code "50") (name "USB_N") (class "Default")
      (node (ref "MCU") (pin "3") (pinfunction "D-_3") (pintype "bidirectional"))
      (node (ref "R19") (pin "2") (pinfunction "2_2") (pintype "passive"))
    )
    (net (code "51") (name "USB_P") (class "Default")
      (node (ref "MCU") (pin "4") (pinfunction "D+_4") (pintype "bidirectional"))
      (node (ref "R20") (pin "2") (pinfunction "2_2") (pintype "passive"))
    )
    (net (code "52") (name "VCC_3V3") (class "Default")
      (node (ref "BARO") (pin "2") (pinfunction "VS_2") (pintype "power_in"))
      (node (ref "C1") (pin "1") (pinfunction "1_1") (pintype "passive"))
      (node (ref "C15") (pin "2") (pinfunction "2_2") (pintype "passive"))
      (node (ref "C17") (pin "+") (pinfunction "+_+") (pintype "passive"))
      (node (ref "C18") (pin "+") (pinfunction "+_+") (pintype "passive"))
      (node (ref "C19") (pin "+") (pinfunction "+_+") (pintype "passive"))
      (node (ref "C2") (pin "1") (pinfunction "1_1") (pintype "passive"))
      (node (ref "C3") (pin "1") (pinfunction "1_1") (pintype "passive"))
      (node (ref "C4") (pin "1") (pinfunction "1_1") (pintype "passive"))
      (node (ref "C5") (pin "1") (pinfunction "1_1") (pintype "passive"))
      (node (ref "C6") (pin "1") (pinfunction "1_1") (pintype "passive"))
      (node (ref "C7") (pin "+") (pinfunction "+_+") (pintype "passive"))
      (node (ref "C8") (pin "1") (pinfunction "1_1") (pintype "passive"))
      (node (ref "C9") (pin "1") (pinfunction "1_1") (pintype "passive"))
      (node (ref "DP0") (pin "2") (pinfunction "VS_2") (pintype "power_in"))
      (node (ref "DPA") (pin "2") (pinfunction "VS_2") (pintype "power_in"))
      (node (ref "DPB") (pin "2") (pinfunction "VS_2") (pintype "power_in"))
      (node (ref "EXT_OAT") (pin "1") (pinfunction "1_1") (pintype "passive"))
      (node (ref "ICSP") (pin "2") (pinfunction "2_2") (pintype "passive"))
      (node (ref "MCU") (pin "14") (pinfunction "VCC_14") (pintype "bidirectional"))
      (node (ref "MCU") (pin "24") (pinfunction "AVCC_24") (pintype "bidirectional"))
      (node (ref "MCU") (pin "34") (pinfunction "VCC_34") (pintype "bidirectional"))
      (node (ref "MCU") (pin "44") (pinfunction "AVCC_44") (pintype "bidirectional"))
      (node (ref "MUX") (pin "24") (pinfunction "VCC_24") (pintype "bidirectional"))
      (node (ref "OAT") (pin "8") (pinfunction "VCC_8") (pintype "power_in"))
      (node (ref "R1") (pin "2") (pinfunction "2_2") (pintype "passive"))
      (node (ref "R10") (pin "2") (pinfunction "2_2") (pintype "passive"))
      (node (ref "R14") (pin "2") (pinfunction "2_2") (pintype "passive"))
      (node (ref "R16") (pin "2") (pinfunction "2_2") (pintype "passive"))
      (node (ref "R17") (pin "2") (pinfunction "2_2") (pintype "passive"))
      (node (ref "R2") (pin "2") (pinfunction "2_2") (pintype "passive"))
      (node (ref "R21") (pin "2") (pinfunction "2_2") (pintype "passive"))
      (node (ref "R22") (pin "2") (pinfunction "2_2") (pintype "passive"))
      (node (ref "R23") (pin "1") (pinfunction "1_1") (pintype "passive"))
      (node (ref "R3") (pin "2") (pinfunction "2_2") (pintype "passive"))
      (node (ref "R4") (pin "2") (pinfunction "2_2") (pintype "passive"))
      (node (ref "R5") (pin "2") (pinfunction "2_2") (pintype "passive"))
      (node (ref "R6") (pin "2") (pinfunction "2_2") (pintype "passive"))
      (node (ref "R7") (pin "2") (pinfunction "2_2") (pintype "passive"))
      (node (ref "R8") (pin "2") (pinfunction "2_2") (pintype "passive"))
      (node (ref "R9") (pin "2") (pinfunction "2_2") (pintype "passive"))
      (node (ref "VREG") (pin "3") (pinfunction "OUT_3") (pintype "power_in"))
      (node (ref "XBEE") (pin "1") (pinfunction "VCC_1") (pintype "power_in"))
    )
    (net (code "53") (name "VCC_5V0") (class "Default")
      (node (ref "C13") (pin "2") (pinfunction "2_2") (pintype "passive"))
      (node (ref "CC") (pin "4") (pinfunction "VIN_4") (pintype "power_in"))
      (node (ref "F1") (pin "2") (pinfunction "2_2") (pintype "bidirectional"))
      (node (ref "MCU") (pin "2") (pinfunction "UVCC_2") (pintype "bidirectional"))
      (node (ref "MCU") (pin "7") (pinfunction "VBUS_7") (pintype "bidirectional"))
    )
    (net (code "54") (name "unconnected-(BM-PIO-Pad8)") (class "Default")
      (node (ref "BM") (pin "8") (pinfunction "PIO_8") (pintype "bidirectional"))
    )
    (net (code "55") (name "unconnected-(J1-PAD1-PadNC1)") (class "Default")
      (node (ref "J1") (pin "NC1") (pinfunction "PAD1_NC1") (pintype "bidirectional"))
    )
    (net (code "56") (name "unconnected-(J1-PAD2-PadNC2)") (class "Default")
      (node (ref "J1") (pin "NC2") (pinfunction "PAD2_NC2") (pintype "bidirectional"))
    )
    (net (code "57") (name "unconnected-(JP1-ID-Pad4)") (class "Default")
      (node (ref "JP1") (pin "4") (pinfunction "ID_4") (pintype "bidirectional"))
    )
    (net (code "58") (name "unconnected-(MCU-PB4(ADC11)-Pad28)") (class "Default")
      (node (ref "MCU") (pin "28") (pinfunction "PB4(ADC11)_28") (pintype "bidirectional"))
    )
    (net (code "59") (name "unconnected-(MCU-PB5(ADC12)-Pad29)") (class "Default")
      (node (ref "MCU") (pin "29") (pinfunction "PB5(ADC12)_29") (pintype "bidirectional"))
    )
    (net (code "60") (name "unconnected-(MCU-PB6(ADC13)-Pad30)") (class "Default")
      (node (ref "MCU") (pin "30") (pinfunction "PB6(ADC13)_30") (pintype "bidirectional"))
    )
    (net (code "61") (name "unconnected-(MCU-PB7-Pad12)") (class "Default")
      (node (ref "MCU") (pin "12") (pinfunction "PB7_12") (pintype "bidirectional"))
    )
    (net (code "62") (name "unconnected-(MCU-PC6-Pad31)") (class "Default")
      (node (ref "MCU") (pin "31") (pinfunction "PC6_31") (pintype "bidirectional"))
    )
    (net (code "63") (name "unconnected-(MCU-PC7-Pad32)") (class "Default")
      (node (ref "MCU") (pin "32") (pinfunction "PC7_32") (pintype "bidirectional"))
    )
    (net (code "64") (name "unconnected-(MCU-PD6(ADC9)-Pad26)") (class "Default")
      (node (ref "MCU") (pin "26") (pinfunction "PD6(ADC9)_26") (pintype "bidirectional"))
    )
    (net (code "65") (name "unconnected-(MCU-PD7(ADC10)-Pad27)") (class "Default")
      (node (ref "MCU") (pin "27") (pinfunction "PD7(ADC10)_27") (pintype "bidirectional"))
    )
    (net (code "66") (name "unconnected-(MCU-PE6-Pad1)") (class "Default")
      (node (ref "MCU") (pin "1") (pinfunction "PE6_1") (pintype "bidirectional"))
    )
    (net (code "67") (name "unconnected-(MCU-PF1(ADC1)-Pad40)") (class "Default")
      (node (ref "MCU") (pin "40") (pinfunction "PF1(ADC1)_40") (pintype "bidirectional"))
    )
    (net (code "68") (name "unconnected-(MCU-PF4(ADC4)-Pad39)") (class "Default")
      (node (ref "MCU") (pin "39") (pinfunction "PF4(ADC4)_39") (pintype "bidirectional"))
    )
    (net (code "69") (name "unconnected-(MCU-PF5(ADC5)-Pad38)") (class "Default")
      (node (ref "MCU") (pin "38") (pinfunction "PF5(ADC5)_38") (pintype "bidirectional"))
    )
    (net (code "70") (name "unconnected-(MCU-PF6(ADC6)-Pad37)") (class "Default")
      (node (ref "MCU") (pin "37") (pinfunction "PF6(ADC6)_37") (pintype "bidirectional"))
    )
    (net (code "71") (name "unconnected-(MCU-PF7(ADC7)-Pad36)") (class "Default")
      (node (ref "MCU") (pin "36") (pinfunction "PF7(ADC7)_36") (pintype "bidirectional"))
    )
    (net (code "72") (name "unconnected-(MUX-SC5-Pad16)") (class "Default")
      (node (ref "MUX") (pin "16") (pinfunction "SC5_16") (pintype "bidirectional"))
    )
    (net (code "73") (name "unconnected-(MUX-SC6-Pad18)") (class "Default")
      (node (ref "MUX") (pin "18") (pinfunction "SC6_18") (pintype "bidirectional"))
    )
    (net (code "74") (name "unconnected-(MUX-SD5-Pad15)") (class "Default")
      (node (ref "MUX") (pin "15") (pinfunction "SD5_15") (pintype "bidirectional"))
    )
    (net (code "75") (name "unconnected-(MUX-SD6-Pad17)") (class "Default")
      (node (ref "MUX") (pin "17") (pinfunction "SD6_17") (pintype "bidirectional"))
    )
    (net (code "76") (name "unconnected-(OAT-ALERT-Pad3)") (class "Default")
      (node (ref "OAT") (pin "3") (pinfunction "ALERT_3") (pintype "output"))
    )
    (net (code "77") (name "unconnected-(S1-S-Pad3)") (class "Default")
      (node (ref "S1") (pin "3") (pinfunction "S_3") (pintype "passive"))
    )
    (net (code "78") (name "unconnected-(XBEE-AD0{slash}DIO0-Pad20)") (class "Default")
      (node (ref "XBEE") (pin "20") (pinfunction "AD0/DIO0_20") (pintype "bidirectional"))
    )
    (net (code "79") (name "unconnected-(XBEE-AD1{slash}DIO1-Pad19)") (class "Default")
      (node (ref "XBEE") (pin "19") (pinfunction "AD1/DIO1_19") (pintype "bidirectional"))
    )
    (net (code "80") (name "unconnected-(XBEE-AD2{slash}DIO2-Pad18)") (class "Default")
      (node (ref "XBEE") (pin "18") (pinfunction "AD2/DIO2_18") (pintype "bidirectional"))
    )
    (net (code "81") (name "unconnected-(XBEE-CD{slash}DOUT_EN{slash}DO8-Pad4)") (class "Default")
      (node (ref "XBEE") (pin "4") (pinfunction "CD/DOUT_EN/DO8_4") (pintype "output"))
    )
    (net (code "82") (name "unconnected-(XBEE-COORD_SEL{slash}AD3{slash}DIO3-Pad17)") (class "Default")
      (node (ref "XBEE") (pin "17") (pinfunction "COORD_SEL/AD3/DIO3_17") (pintype "bidirectional"))
    )
    (net (code "83") (name "unconnected-(XBEE-RF_TX{slash}AD4{slash}DIO4-Pad11)") (class "Default")
      (node (ref "XBEE") (pin "11") (pinfunction "RF_TX/AD4/DIO4_11") (pintype "bidirectional"))
    )
    (net (code "84") (name "unconnected-(XBEE-VREF-Pad14)") (class "Default")
      (node (ref "XBEE") (pin "14") (pinfunction "VREF_14") (pintype "input"))
    )
    (net (code "85") (name "unconnected-(XBEE-~{CTS}{slash}DIO7-Pad12)") (class "Default")
      (node (ref "XBEE") (pin "12") (pinfunction "~{CTS}/DIO7_12") (pintype "bidirectional"))
    )
    (net (code "86") (name "unconnected-(XBEE-~{DTR}{slash}SLEEP_RQ{slash}DI8-Pad9)") (class "Default")
      (node (ref "XBEE") (pin "9") (pinfunction "~{DTR}/SLEEP_RQ/DI8_9") (pintype "bidirectional"))
    )
    (net (code "87") (name "unconnected-(XBEE-~{RESET}-Pad5)") (class "Default")
      (node (ref "XBEE") (pin "5") (pinfunction "~{RESET}_5") (pintype "input"))
    )
    (net (code "88") (name "unconnected-(XBEE-~{RTS}{slash}AD6{slash}DIO6-Pad16)") (class "Default")
      (node (ref "XBEE") (pin "16") (pinfunction "~{RTS}/AD6/DIO6_16") (pintype "bidirectional"))
    )
  )
)
